# GLCD.net
KiCad netlist of a schematic drawn in Altium Designer
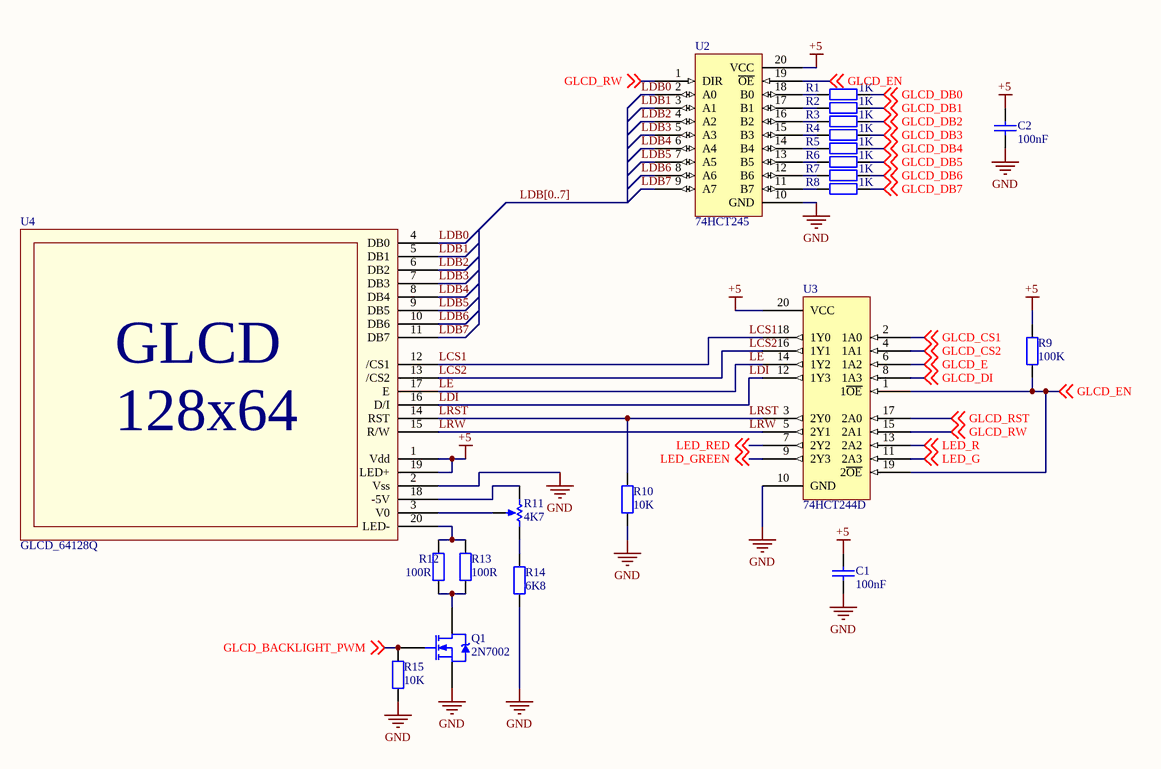
[diagram p0: GLCD.SchDoc]

(export (version "E")
  (design (tool "Eeschema 10.0.6"))
  (components
    (comp (ref "C1")
      (value "100nF")
      (footprint "FP_0805_CAP_085")
      (description "Capacitor")
      (fields (field (name "TOLERANCE") "10%") (field (name "VOLTAGE") "50V"))
      (libsource (lib "hallglib") (part "CAP 100nF"))
    )
    (comp (ref "C2")
      (value "100nF")
      (footprint "FP_0805_CAP_085")
      (description "Capacitor")
      (fields (field (name "TOLERANCE") "10%") (field (name "VOLTAGE") "50V"))
      (libsource (lib "hallglib") (part "CAP 100nF"))
    )
    (comp (ref "Q1")
      (value "2N7002")
      (footprint "FP_SOT23-3")
      (description "N-channel MOSFET")
      (fields (field (name "VOLTAGE") "60V"))
      (libsource (lib "hallglib") (part "2N7002"))
    )
    (comp (ref "R1")
      (value "1K")
      (footprint "FP_0805_RES")
      (description "Resistor")
      (fields (field (name "TOLERANCE") "5%") (field (name "POWER") "125mW"))
      (libsource (lib "hallglib") (part "RES 1K"))
    )
    (comp (ref "R2")
      (value "1K")
      (footprint "FP_0805_RES")
      (description "Resistor")
      (fields (field (name "TOLERANCE") "5%") (field (name "POWER") "125mW"))
      (libsource (lib "hallglib") (part "RES 1K"))
    )
    (comp (ref "R3")
      (value "1K")
      (footprint "FP_0805_RES")
      (description "Resistor")
      (fields (field (name "TOLERANCE") "5%") (field (name "POWER") "125mW"))
      (libsource (lib "hallglib") (part "RES 1K"))
    )
    (comp (ref "R4")
      (value "1K")
      (footprint "FP_0805_RES")
      (description "Resistor")
      (fields (field (name "TOLERANCE") "5%") (field (name "POWER") "125mW"))
      (libsource (lib "hallglib") (part "RES 1K"))
    )
    (comp (ref "R5")
      (value "1K")
      (footprint "FP_0805_RES")
      (description "Resistor")
      (fields (field (name "TOLERANCE") "5%") (field (name "POWER") "125mW"))
      (libsource (lib "hallglib") (part "RES 1K"))
    )
    (comp (ref "R6")
      (value "1K")
      (footprint "FP_0805_RES")
      (description "Resistor")
      (fields (field (name "TOLERANCE") "5%") (field (name "POWER") "125mW"))
      (libsource (lib "hallglib") (part "RES 1K"))
    )
    (comp (ref "R7")
      (value "1K")
      (footprint "FP_0805_RES")
      (description "Resistor")
      (fields (field (name "TOLERANCE") "5%") (field (name "POWER") "125mW"))
      (libsource (lib "hallglib") (part "RES 1K"))
    )
    (comp (ref "R8")
      (value "1K")
      (footprint "FP_0805_RES")
      (description "Resistor")
      (fields (field (name "TOLERANCE") "5%") (field (name "POWER") "125mW"))
      (libsource (lib "hallglib") (part "RES 1K"))
    )
    (comp (ref "R9")
      (value "100K")
      (footprint "FP_0805_RES")
      (description "Resistor")
      (fields (field (name "TOLERANCE") "5%") (field (name "POWER") "125mW"))
      (libsource (lib "hallglib") (part "RES 100K"))
    )
    (comp (ref "R10")
      (value "10K")
      (footprint "FP_0805_RES")
      (description "Resistor")
      (fields (field (name "TOLERANCE") "5%") (field (name "POWER") "125mW"))
      (libsource (lib "") (part "RES 10K_1"))
    )
    (comp (ref "R11")
      (value "4K7")
      (footprint "FP_CERMET_SMD")
      (description "4K70 3305-472R (KIC) 3x3.8mm CERMET")
      (libsource (lib "hallglib") (part "Cermet Pot 4K7"))
    )
    (comp (ref "R12")
      (value "100R")
      (footprint "FP_0805_RES")
      (description "Resistor")
      (fields (field (name "TOLERANCE") "5%") (field (name "POWER") "125mW"))
      (libsource (lib "hallglib") (part "RES 100R"))
    )
    (comp (ref "R13")
      (value "100R")
      (footprint "FP_0805_RES")
      (description "Resistor")
      (fields (field (name "TOLERANCE") "5%") (field (name "POWER") "125mW"))
      (libsource (lib "hallglib") (part "RES 100R"))
    )
    (comp (ref "R14")
      (value "6K8")
      (footprint "FP_0805_RES")
      (description "Resistor")
      (fields (field (name "TOLERANCE") "5%") (field (name "POWER") "125mW"))
      (libsource (lib "hallglib") (part "RES 6K8"))
    )
    (comp (ref "R15")
      (value "10K")
      (footprint "FP_0805_RES")
      (description "Resistor")
      (fields (field (name "TOLERANCE") "5%") (field (name "POWER") "125mW"))
      (libsource (lib "hallglib") (part "RES 10K"))
    )
    (comp (ref "U2")
      (value "74HCT245")
      (footprint "FP_SOP127P1030X265-20M")
      (description "8x Bidirectional bus transciever")
      (libsource (lib "hallglib") (part "74HCT245"))
    )
    (comp (ref "U3")
      (value "74HCT244D")
      (footprint "FP_SOP127P1030X265-20M")
      (description "8xBuffer/Line Driver")
      (libsource (lib "hallglib") (part "74HCT244D"))
    )
    (comp (ref "U4")
      (value "GLCD_64128Q")
      (footprint "FP_GLCD_64128Q")
      (description "64128QCCBW-3LP")
      (libsource (lib "hallglib") (part "GLCD_64128Q"))
    )
  )
  (nets
    (net (code "1") (name "+5") (class "Default")
      (node (ref "C1") (pin "2") (pinfunction "2_2") (pintype "passive"))
      (node (ref "C2") (pin "2") (pinfunction "2_2") (pintype "passive"))
      (node (ref "R9") (pin "2") (pinfunction "2_2") (pintype "passive"))
      (node (ref "U2") (pin "20") (pinfunction "VCC_20") (pintype "power_in"))
      (node (ref "U3") (pin "20") (pinfunction "VCC_20") (pintype "power_in"))
      (node (ref "U4") (pin "1") (pinfunction "Vdd_1") (pintype "passive"))
      (node (ref "U4") (pin "19") (pinfunction "LED+_19") (pintype "passive"))
    )
    (net (code "2") (name "/LCS1") (class "Default")
      (node (ref "U3") (pin "18") (pinfunction "1Y0_18") (pintype "output"))
      (node (ref "U4") (pin "12") (pinfunction "/CS1_12") (pintype "passive"))
    )
    (net (code "3") (name "/LCS2") (class "Default")
      (node (ref "U3") (pin "16") (pinfunction "1Y1_16") (pintype "output"))
      (node (ref "U4") (pin "13") (pinfunction "/CS2_13") (pintype "passive"))
    )
    (net (code "4") (name "/LDB0") (class "Default")
      (node (ref "U2") (pin "2") (pinfunction "A0_2") (pintype "bidirectional"))
      (node (ref "U4") (pin "4") (pinfunction "DB0_4") (pintype "passive"))
    )
    (net (code "5") (name "/LDB1") (class "Default")
      (node (ref "U2") (pin "3") (pinfunction "A1_3") (pintype "bidirectional"))
      (node (ref "U4") (pin "5") (pinfunction "DB1_5") (pintype "passive"))
    )
    (net (code "6") (name "/LDB2") (class "Default")
      (node (ref "U2") (pin "4") (pinfunction "A2_4") (pintype "bidirectional"))
      (node (ref "U4") (pin "6") (pinfunction "DB2_6") (pintype "passive"))
    )
    (net (code "7") (name "/LDB3") (class "Default")
      (node (ref "U2") (pin "5") (pinfunction "A3_5") (pintype "bidirectional"))
      (node (ref "U4") (pin "7") (pinfunction "DB3_7") (pintype "passive"))
    )
    (net (code "8") (name "/LDB4") (class "Default")
      (node (ref "U2") (pin "6") (pinfunction "A4_6") (pintype "bidirectional"))
      (node (ref "U4") (pin "8") (pinfunction "DB4_8") (pintype "passive"))
    )
    (net (code "9") (name "/LDB5") (class "Default")
      (node (ref "U2") (pin "7") (pinfunction "A5_7") (pintype "bidirectional"))
      (node (ref "U4") (pin "9") (pinfunction "DB5_9") (pintype "passive"))
    )
    (net (code "10") (name "/LDB6") (class "Default")
      (node (ref "U2") (pin "8") (pinfunction "A6_8") (pintype "bidirectional"))
      (node (ref "U4") (pin "10") (pinfunction "DB6_10") (pintype "passive"))
    )
    (net (code "11") (name "/LDB7") (class "Default")
      (node (ref "U2") (pin "9") (pinfunction "A7_9") (pintype "bidirectional"))
      (node (ref "U4") (pin "11") (pinfunction "DB7_11") (pintype "passive"))
    )
    (net (code "13") (name "/LDI") (class "Default")
      (node (ref "U3") (pin "12") (pinfunction "1Y3_12") (pintype "output"))
      (node (ref "U4") (pin "16") (pinfunction "D/I_16") (pintype "passive"))
    )
    (net (code "14") (name "/LE") (class "Default")
      (node (ref "U3") (pin "14") (pinfunction "1Y2_14") (pintype "output"))
      (node (ref "U4") (pin "17") (pinfunction "E_17") (pintype "passive"))
    )
    (net (code "15") (name "/LRST") (class "Default")
      (node (ref "R10") (pin "2") (pinfunction "2_2") (pintype "passive"))
      (node (ref "U3") (pin "3") (pinfunction "2Y0_3") (pintype "output"))
      (node (ref "U4") (pin "14") (pinfunction "RST_14") (pintype "passive"))
    )
    (net (code "16") (name "/LRW") (class "Default")
      (node (ref "U3") (pin "5") (pinfunction "2Y1_5") (pintype "output"))
      (node (ref "U4") (pin "15") (pinfunction "R/W_15") (pintype "passive"))
    )
    (net (code "17") (name "GLCD_BACKLIGHT_PWM") (class "Default")
      (node (ref "Q1") (pin "1") (pinfunction "G_1") (pintype "passive"))
      (node (ref "R15") (pin "2") (pinfunction "2_2") (pintype "passive"))
    )
    (net (code "18") (name "GLCD_CS1") (class "Default")
      (node (ref "U3") (pin "2") (pinfunction "1A0_2") (pintype "input"))
    )
    (net (code "19") (name "GLCD_CS2") (class "Default")
      (node (ref "U3") (pin "4") (pinfunction "1A1_4") (pintype "input"))
    )
    (net (code "20") (name "GLCD_DB0") (class "Default")
      (node (ref "R1") (pin "2") (pinfunction "2_2") (pintype "passive"))
    )
    (net (code "21") (name "GLCD_DB1") (class "Default")
      (node (ref "R2") (pin "2") (pinfunction "2_2") (pintype "passive"))
    )
    (net (code "22") (name "GLCD_DB2") (class "Default")
      (node (ref "R3") (pin "2") (pinfunction "2_2") (pintype "passive"))
    )
    (net (code "23") (name "GLCD_DB3") (class "Default")
      (node (ref "R4") (pin "2") (pinfunction "2_2") (pintype "passive"))
    )
    (net (code "24") (name "GLCD_DB4") (class "Default")
      (node (ref "R5") (pin "2") (pinfunction "2_2") (pintype "passive"))
    )
    (net (code "25") (name "GLCD_DB5") (class "Default")
      (node (ref "R6") (pin "2") (pinfunction "2_2") (pintype "passive"))
    )
    (net (code "26") (name "GLCD_DB6") (class "Default")
      (node (ref "R7") (pin "2") (pinfunction "2_2") (pintype "passive"))
    )
    (net (code "27") (name "GLCD_DB7") (class "Default")
      (node (ref "R8") (pin "2") (pinfunction "2_2") (pintype "passive"))
    )
    (net (code "28") (name "GLCD_DI") (class "Default")
      (node (ref "U3") (pin "8") (pinfunction "1A3_8") (pintype "input"))
    )
    (net (code "29") (name "GLCD_E") (class "Default")
      (node (ref "U3") (pin "6") (pinfunction "1A2_6") (pintype "input"))
    )
    (net (code "30") (name "GLCD_EN") (class "Default")
      (node (ref "R9") (pin "1") (pinfunction "1_1") (pintype "passive"))
      (node (ref "U2") (pin "19") (pinfunction "~{OE}_19") (pintype "input"))
      (node (ref "U3") (pin "1") (pinfunction "1~{OE}_1") (pintype "input"))
      (node (ref "U3") (pin "19") (pinfunction "2~{OE}_19") (pintype "input"))
    )
    (net (code "31") (name "GLCD_RST") (class "Default")
      (node (ref "U3") (pin "17") (pinfunction "2A0_17") (pintype "input"))
    )
    (net (code "32") (name "GLCD_RW") (class "Default")
      (node (ref "U2") (pin "1") (pinfunction "DIR_1") (pintype "input"))
      (node (ref "U3") (pin "15") (pinfunction "2A1_15") (pintype "input"))
    )
    (net (code "33") (name "GND") (class "Default")
      (node (ref "C1") (pin "1") (pinfunction "1_1") (pintype "passive"))
      (node (ref "C2") (pin "1") (pinfunction "1_1") (pintype "passive"))
      (node (ref "Q1") (pin "3") (pinfunction "S_3") (pintype "passive"))
      (node (ref "R10") (pin "1") (pinfunction "1_1") (pintype "passive"))
      (node (ref "R14") (pin "1") (pinfunction "1_1") (pintype "passive"))
      (node (ref "R15") (pin "1") (pinfunction "1_1") (pintype "passive"))
      (node (ref "U2") (pin "10") (pinfunction "GND_10") (pintype "power_in"))
      (node (ref "U3") (pin "10") (pinfunction "GND_10") (pintype "power_in"))
      (node (ref "U4") (pin "2") (pinfunction "Vss_2") (pintype "passive"))
    )
    (net (code "34") (name "LED_G") (class "Default")
      (node (ref "U3") (pin "11") (pinfunction "2A3_11") (pintype "input"))
    )
    (net (code "35") (name "LED_GREEN") (class "Default")
      (node (ref "U3") (pin "9") (pinfunction "2Y3_9") (pintype "output"))
    )
    (net (code "36") (name "LED_R") (class "Default")
      (node (ref "U3") (pin "13") (pinfunction "2A2_13") (pintype "input"))
    )
    (net (code "37") (name "LED_RED") (class "Default")
      (node (ref "U3") (pin "7") (pinfunction "2Y2_7") (pintype "output"))
    )
    (net (code "38") (name "Net-(Q1-D)") (class "Default")
      (node (ref "Q1") (pin "2") (pinfunction "D_2") (pintype "passive"))
      (node (ref "R12") (pin "1") (pinfunction "1_1") (pintype "passive"))
      (node (ref "R13") (pin "1") (pinfunction "1_1") (pintype "passive"))
    )
    (net (code "39") (name "Net-(R11-CCW)") (class "Default")
      (node (ref "R11") (pin "1") (pinfunction "CCW_1") (pintype "passive"))
      (node (ref "U4") (pin "18") (pinfunction "-5V_18") (pintype "passive"))
    )
    (net (code "40") (name "Net-(R11-CW)") (class "Default")
      (node (ref "R11") (pin "3") (pinfunction "CW_3") (pintype "passive"))
      (node (ref "R14") (pin "2") (pinfunction "2_2") (pintype "passive"))
    )
    (net (code "41") (name "Net-(R11-WIPER)") (class "Default")
      (node (ref "R11") (pin "2") (pinfunction "WIPER_2") (pintype "passive"))
      (node (ref "U4") (pin "3") (pinfunction "V0_3") (pintype "passive"))
    )
    (net (code "42") (name "Net-(U2-B0)") (class "Default")
      (node (ref "R1") (pin "1") (pinfunction "1_1") (pintype "passive"))
      (node (ref "U2") (pin "18") (pinfunction "B0_18") (pintype "bidirectional"))
    )
    (net (code "43") (name "Net-(U2-B1)") (class "Default")
      (node (ref "R2") (pin "1") (pinfunction "1_1") (pintype "passive"))
      (node (ref "U2") (pin "17") (pinfunction "B1_17") (pintype "bidirectional"))
    )
    (net (code "44") (name "Net-(U2-B2)") (class "Default")
      (node (ref "R3") (pin "1") (pinfunction "1_1") (pintype "passive"))
      (node (ref "U2") (pin "16") (pinfunction "B2_16") (pintype "bidirectional"))
    )
    (net (code "45") (name "Net-(U2-B3)") (class "Default")
      (node (ref "R4") (pin "1") (pinfunction "1_1") (pintype "passive"))
      (node (ref "U2") (pin "15") (pinfunction "B3_15") (pintype "bidirectional"))
    )
    (net (code "46") (name "Net-(U2-B4)") (class "Default")
      (node (ref "R5") (pin "1") (pinfunction "1_1") (pintype "passive"))
      (node (ref "U2") (pin "14") (pinfunction "B4_14") (pintype "bidirectional"))
    )
    (net (code "47") (name "Net-(U2-B5)") (class "Default")
      (node (ref "R6") (pin "1") (pinfunction "1_1") (pintype "passive"))
      (node (ref "U2") (pin "13") (pinfunction "B5_13") (pintype "bidirectional"))
    )
    (net (code "48") (name "Net-(U2-B6)") (class "Default")
      (node (ref "R7") (pin "1") (pinfunction "1_1") (pintype "passive"))
      (node (ref "U2") (pin "12") (pinfunction "B6_12") (pintype "bidirectional"))
    )
    (net (code "49") (name "Net-(U2-B7)") (class "Default")
      (node (ref "R8") (pin "1") (pinfunction "1_1") (pintype "passive"))
      (node (ref "U2") (pin "11") (pinfunction "B7_11") (pintype "bidirectional"))
    )
    (net (code "50") (name "Net-(U4-LED-)") (class "Default")
      (node (ref "R12") (pin "2") (pinfunction "2_2") (pintype "passive"))
      (node (ref "R13") (pin "2") (pinfunction "2_2") (pintype "passive"))
      (node (ref "U4") (pin "20") (pinfunction "LED-_20") (pintype "passive"))
    )
  )
)
